# 2.net
KiCad netlist of a schematic drawn in Altium Designer
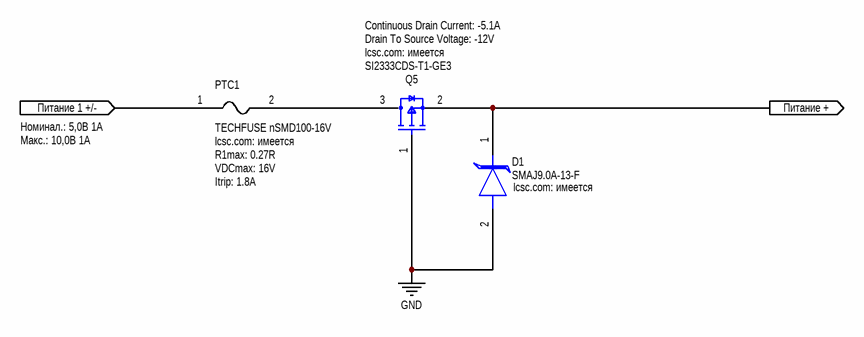
[diagram p0: Блок2.SchDoc]

(export (version "E")
  (design (tool "Eeschema 10.0.6"))
  (components
    (comp (ref "D1")
      (value "SMAJ9.0A-13-F")
      (footprint "FP-SMA-MFG")
      (description "TVS DIODE 9V 15.4V SMA")
      (fields
        (field (name "OCTOPART") "https://octopart.com/smaj9.0a-13-f-diodes+inc.-350369")
        (field (name "MANUFACTURER") "Diodes Inc")
        (field (name "LCSC.COM") "имеется")
      )
      (libsource (lib "Altium Content Vault") (part "e2a1dd67f652bf44a5c14c718bbe709"))
    )
    (comp (ref "PTC1")
      (value "TECHFUSE nSMD100-16V")
      (footprint "nSMD100-16V")
      (fields
        (field (name "LCSC.COM") "имеется")
        (field (name "R1MAX") "0.27R")
        (field (name "VDCMAX") "16V")
        (field (name "ITRIP") "1.8A")
      )
      (libsource (lib "lcsc") (part "TECHFUSE nSMD100-16V"))
    )
    (comp (ref "Q5")
      (value "SI2333CDS-T1-GE3")
      (footprint "FP-S-03946-MFG")
      (description "MOSFET P-CH 12V 7.1A SOT-23")
      (fields
        (field (name "OCTOPART") "https://octopart.com/si2333cds-t1-ge3-vishay-43171447")
        (field (name "CONTINUOUS DRAIN CURRENT") "-5.1A")
        (field (name "DRAIN TO SOURCE VOLTAGE") "-12V")
        (field (name "MANUFACTURER") "Vishay")
        (field (name "LCSC.COM") "имеется")
      )
      (libsource (lib "Altium Content Vault") (part "82990a719980ad1ba254f3931bce451"))
    )
  )
  (nets
    (net (code "1") (name "/Питание +") (class "Default")
      (node (ref "D1") (pin "1") (pinfunction "C_1") (pintype "passive"))
      (node (ref "Q5") (pin "2") (pinfunction "S_2") (pintype "passive"))
    )
    (net (code "2") (name "/Питание 1 +{slash}-") (class "Default")
      (node (ref "PTC1") (pin "1") (pinfunction "1_1") (pintype "passive"))
    )
    (net (code "3") (name "GND") (class "Default")
      (node (ref "D1") (pin "2") (pinfunction "A_2") (pintype "passive"))
      (node (ref "Q5") (pin "1") (pinfunction "G_1") (pintype "passive"))
    )
    (net (code "4") (name "Net-(Q5-D)") (class "Default")
      (node (ref "PTC1") (pin "2") (pinfunction "2_2") (pintype "passive"))
      (node (ref "Q5") (pin "3") (pinfunction "D_3") (pintype "passive"))
    )
  )
)
